# Analog-Digital-Mux-Breakout.net
KiCad netlist of a schematic drawn in EAGLE
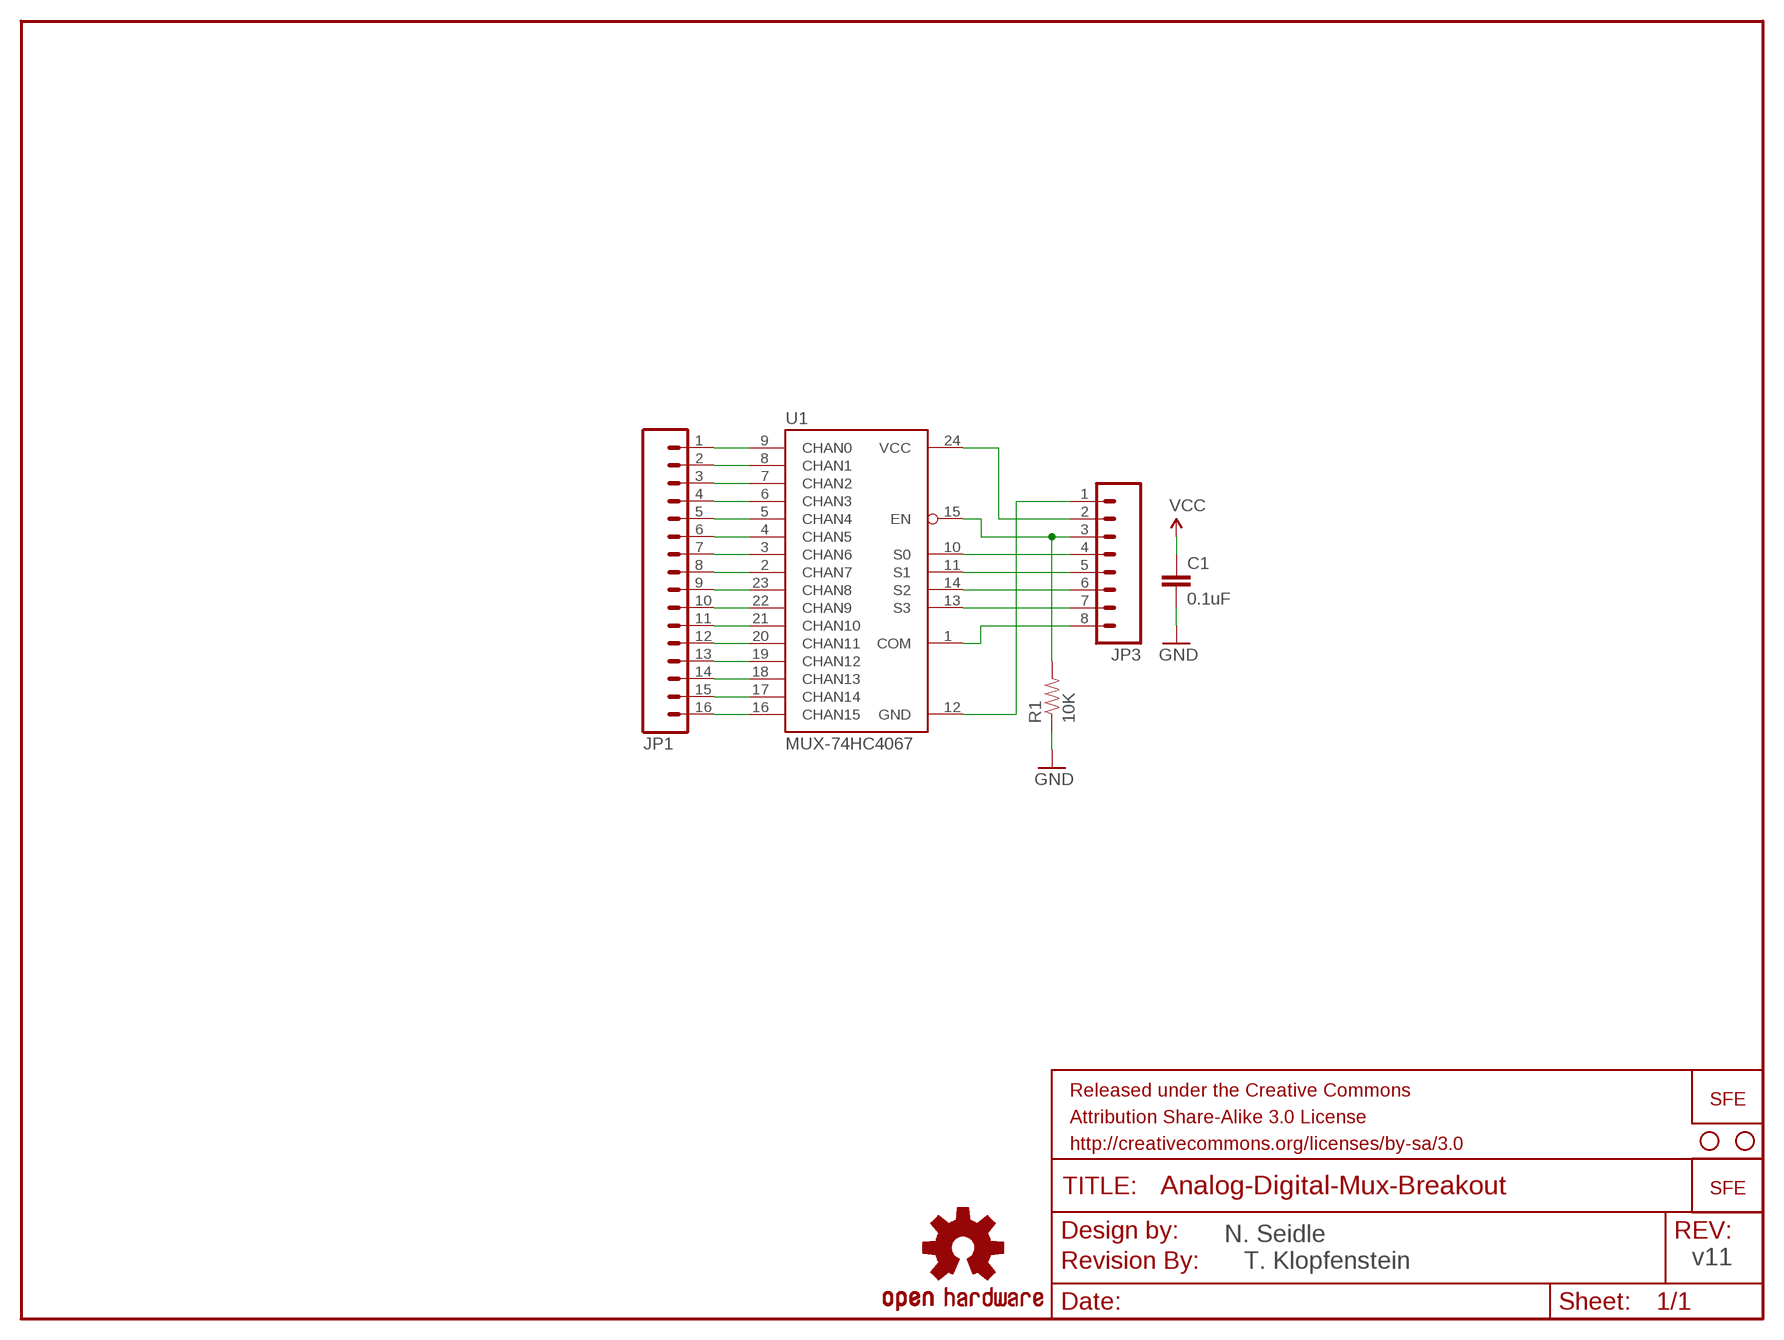
[diagram p0: schematic, sheet 1]

(export (version "E")
  (design (tool "Eeschema 10.0.6"))
  (components
    (comp (ref "C1")
      (value "0.1uF")
      (footprint "eagle-import:0603")
      (libsource (lib "eagle-import") (part "CAP0603"))
    )
    (comp (ref "FRAME1")
      (value "FRAME-LETTER")
      (footprint "eagle-import:CREATIVE_COMMONS")
      (libsource (lib "eagle-import") (part "FRAME-LETTER"))
    )
    (comp (ref "JP1")
      (value "M16PTH")
      (footprint "eagle-import:1X16")
      (libsource (lib "eagle-import") (part "M16PTH"))
    )
    (comp (ref "JP3")
      (value "M081X08")
      (footprint "eagle-import:1X08")
      (libsource (lib "eagle-import") (part "M081X08"))
    )
    (comp (ref "LOGO1")
      (value "OSHW-LOGOL")
      (footprint "eagle-import:OSHW-LOGO-L")
      (libsource (lib "eagle-import") (part "OSHW-LOGOL"))
    )
    (comp (ref "LOGO2")
      (value "LOGO-SFESK")
      (footprint "eagle-import:SFE-LOGO-FLAME")
      (libsource (lib "eagle-import") (part "SparkFun-Aesthetics_LOGO-SFESK"))
    )
    (comp (ref "R1")
      (value "10K")
      (footprint "eagle-import:0603")
      (libsource (lib "eagle-import") (part "RESISTOR0603"))
    )
    (comp (ref "STANDOFF1")
      (value "STAND-OFF")
      (footprint "eagle-import:STAND-OFF")
      (libsource (lib "eagle-import") (part "STAND-OFF"))
    )
    (comp (ref "STANDOFF2")
      (value "STAND-OFF")
      (footprint "eagle-import:STAND-OFF")
      (libsource (lib "eagle-import") (part "STAND-OFF"))
    )
    (comp (ref "U$1")
      (value "LOGO-SFENEW")
      (footprint "eagle-import:SFE-NEW-WEBLOGO")
      (libsource (lib "eagle-import") (part "LOGO-SFENEW"))
    )
    (comp (ref "U$2")
      (value "REVISION")
      (footprint "eagle-import:REVISION")
      (libsource (lib "eagle-import") (part "REVISION"))
    )
    (comp (ref "U1")
      (value "MUX-74HC4067")
      (footprint "eagle-import:SSOP24")
      (libsource (lib "eagle-import") (part "MUX-74HC4067SMD"))
    )
  )
  (nets
    (net (code "1") (name "GND") (class "Default")
      (node (ref "C1") (pin "2") (pinfunction "2_2") (pintype "passive"))
      (node (ref "JP3") (pin "1") (pinfunction "1_1") (pintype "passive"))
      (node (ref "R1") (pin "1") (pinfunction "1_1") (pintype "passive"))
      (node (ref "U1") (pin "12") (pinfunction "GND_12") (pintype "bidirectional"))
    )
    (net (code "2") (name "Net-(U1-CHAN0)") (class "Default")
      (node (ref "JP1") (pin "1") (pinfunction "1_1") (pintype "passive"))
      (node (ref "U1") (pin "9") (pinfunction "CHAN0_9") (pintype "bidirectional"))
    )
    (net (code "3") (name "Net-(U1-CHAN1)") (class "Default")
      (node (ref "JP1") (pin "2") (pinfunction "2_2") (pintype "passive"))
      (node (ref "U1") (pin "8") (pinfunction "CHAN1_8") (pintype "bidirectional"))
    )
    (net (code "4") (name "Net-(U1-CHAN2)") (class "Default")
      (node (ref "JP1") (pin "3") (pinfunction "3_3") (pintype "passive"))
      (node (ref "U1") (pin "7") (pinfunction "CHAN2_7") (pintype "bidirectional"))
    )
    (net (code "5") (name "Net-(U1-CHAN3)") (class "Default")
      (node (ref "JP1") (pin "4") (pinfunction "4_4") (pintype "passive"))
      (node (ref "U1") (pin "6") (pinfunction "CHAN3_6") (pintype "bidirectional"))
    )
    (net (code "6") (name "Net-(U1-CHAN4)") (class "Default")
      (node (ref "JP1") (pin "5") (pinfunction "5_5") (pintype "passive"))
      (node (ref "U1") (pin "5") (pinfunction "CHAN4_5") (pintype "bidirectional"))
    )
    (net (code "7") (name "Net-(U1-CHAN5)") (class "Default")
      (node (ref "JP1") (pin "6") (pinfunction "6_6") (pintype "passive"))
      (node (ref "U1") (pin "4") (pinfunction "CHAN5_4") (pintype "bidirectional"))
    )
    (net (code "8") (name "Net-(U1-CHAN6)") (class "Default")
      (node (ref "JP1") (pin "7") (pinfunction "7_7") (pintype "passive"))
      (node (ref "U1") (pin "3") (pinfunction "CHAN6_3") (pintype "bidirectional"))
    )
    (net (code "9") (name "Net-(U1-CHAN7)") (class "Default")
      (node (ref "JP1") (pin "8") (pinfunction "8_8") (pintype "passive"))
      (node (ref "U1") (pin "2") (pinfunction "CHAN7_2") (pintype "bidirectional"))
    )
    (net (code "10") (name "Net-(U1-CHAN8)") (class "Default")
      (node (ref "JP1") (pin "9") (pinfunction "9_9") (pintype "passive"))
      (node (ref "U1") (pin "23") (pinfunction "CHAN8_23") (pintype "bidirectional"))
    )
    (net (code "11") (name "Net-(U1-CHAN9)") (class "Default")
      (node (ref "JP1") (pin "10") (pinfunction "10_10") (pintype "passive"))
      (node (ref "U1") (pin "22") (pinfunction "CHAN9_22") (pintype "bidirectional"))
    )
    (net (code "12") (name "Net-(U1-CHAN10)") (class "Default")
      (node (ref "JP1") (pin "11") (pinfunction "11_11") (pintype "passive"))
      (node (ref "U1") (pin "21") (pinfunction "CHAN10_21") (pintype "bidirectional"))
    )
    (net (code "13") (name "Net-(U1-CHAN11)") (class "Default")
      (node (ref "JP1") (pin "12") (pinfunction "12_12") (pintype "passive"))
      (node (ref "U1") (pin "20") (pinfunction "CHAN11_20") (pintype "bidirectional"))
    )
    (net (code "14") (name "Net-(U1-CHAN12)") (class "Default")
      (node (ref "JP1") (pin "13") (pinfunction "13_13") (pintype "passive"))
      (node (ref "U1") (pin "19") (pinfunction "CHAN12_19") (pintype "bidirectional"))
    )
    (net (code "15") (name "Net-(U1-CHAN13)") (class "Default")
      (node (ref "JP1") (pin "14") (pinfunction "14_14") (pintype "passive"))
      (node (ref "U1") (pin "18") (pinfunction "CHAN13_18") (pintype "bidirectional"))
    )
    (net (code "16") (name "Net-(U1-CHAN14)") (class "Default")
      (node (ref "JP1") (pin "15") (pinfunction "15_15") (pintype "passive"))
      (node (ref "U1") (pin "17") (pinfunction "CHAN14_17") (pintype "bidirectional"))
    )
    (net (code "17") (name "Net-(U1-CHAN15)") (class "Default")
      (node (ref "JP1") (pin "16") (pinfunction "16_16") (pintype "passive"))
      (node (ref "U1") (pin "16") (pinfunction "CHAN15_16") (pintype "bidirectional"))
    )
    (net (code "18") (name "Net-(U1-COM)") (class "Default")
      (node (ref "JP3") (pin "8") (pinfunction "8_8") (pintype "passive"))
      (node (ref "U1") (pin "1") (pinfunction "COM_1") (pintype "bidirectional"))
    )
    (net (code "19") (name "Net-(U1-EN)") (class "Default")
      (node (ref "JP3") (pin "3") (pinfunction "3_3") (pintype "passive"))
      (node (ref "R1") (pin "2") (pinfunction "2_2") (pintype "passive"))
      (node (ref "U1") (pin "15") (pinfunction "EN_15") (pintype "input"))
    )
    (net (code "20") (name "Net-(U1-S0)") (class "Default")
      (node (ref "JP3") (pin "4") (pinfunction "4_4") (pintype "passive"))
      (node (ref "U1") (pin "10") (pinfunction "S0_10") (pintype "input"))
    )
    (net (code "21") (name "Net-(U1-S1)") (class "Default")
      (node (ref "JP3") (pin "5") (pinfunction "5_5") (pintype "passive"))
      (node (ref "U1") (pin "11") (pinfunction "S1_11") (pintype "input"))
    )
    (net (code "22") (name "Net-(U1-S2)") (class "Default")
      (node (ref "JP3") (pin "6") (pinfunction "6_6") (pintype "passive"))
      (node (ref "U1") (pin "14") (pinfunction "S2_14") (pintype "input"))
    )
    (net (code "23") (name "Net-(U1-S3)") (class "Default")
      (node (ref "JP3") (pin "7") (pinfunction "7_7") (pintype "passive"))
      (node (ref "U1") (pin "13") (pinfunction "S3_13") (pintype "input"))
    )
    (net (code "24") (name "VCC") (class "Default")
      (node (ref "C1") (pin "1") (pinfunction "1_1") (pintype "passive"))
      (node (ref "JP3") (pin "2") (pinfunction "2_2") (pintype "passive"))
      (node (ref "U1") (pin "24") (pinfunction "VCC_24") (pintype "bidirectional"))
    )
  )
)
